# handset_adapter.net
KiCad netlist of a schematic drawn in Altium Designer
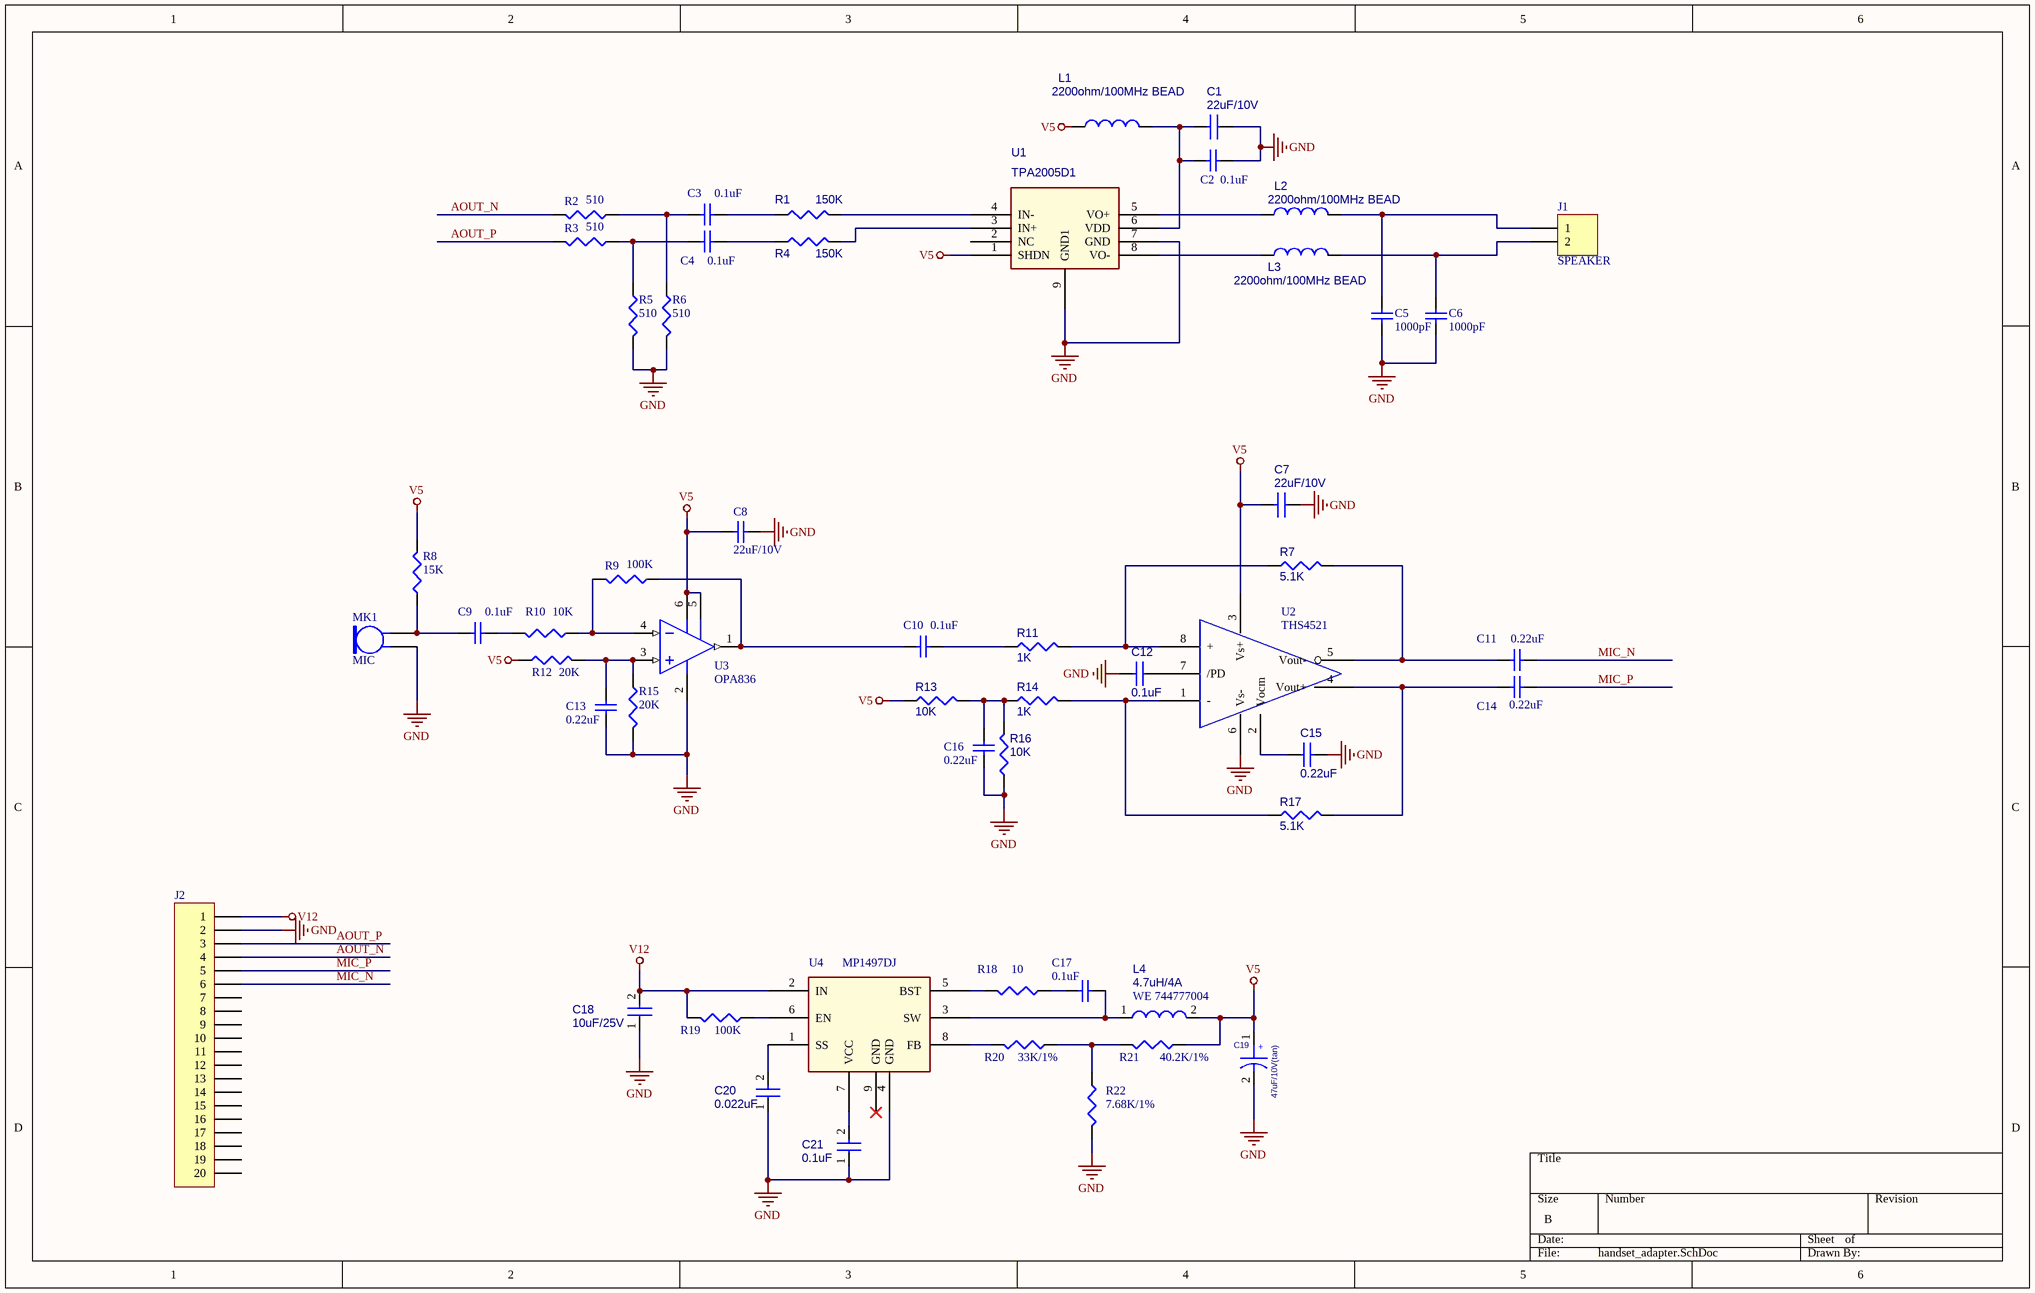
[diagram p0: handset_adapter.SchDoc]

(export (version "E")
  (design (tool "Eeschema 10.0.6"))
  (components
    (comp (ref "C1") (value "22uF/10V") (footprint "1210") (libsource (lib "*") (part "P_CAP NP")))
    (comp (ref "C2")
      (value "0.1uF")
      (footprint "0603")
      (description "Capacitor")
      (libsource (lib "Miscellaneous Devices") (part "Cap"))
    )
    (comp (ref "C3")
      (value "0.1uF")
      (footprint "0603")
      (description "Capacitor")
      (libsource (lib "Miscellaneous Devices") (part "Cap"))
    )
    (comp (ref "C4")
      (value "0.1uF")
      (footprint "0603")
      (description "Capacitor")
      (libsource (lib "Miscellaneous Devices") (part "Cap"))
    )
    (comp (ref "C5")
      (value "1000pF")
      (footprint "0603")
      (description "Capacitor")
      (libsource (lib "Miscellaneous Devices") (part "Cap"))
    )
    (comp (ref "C6")
      (value "1000pF")
      (footprint "0603")
      (description "Capacitor")
      (libsource (lib "Miscellaneous Devices") (part "Cap"))
    )
    (comp (ref "C7") (value "22uF/10V") (footprint "1210") (libsource (lib "*") (part "P_CAP NP")))
    (comp (ref "C8")
      (value "22uF/10V")
      (footprint "1210")
      (description "Capacitor")
      (libsource (lib "Miscellaneous Devices") (part "Cap"))
    )
    (comp (ref "C9")
      (value "0.1uF")
      (footprint "0603")
      (description "Capacitor")
      (libsource (lib "Miscellaneous Devices") (part "Cap"))
    )
    (comp (ref "C10")
      (value "0.1uF")
      (footprint "0603")
      (description "Capacitor")
      (libsource (lib "Miscellaneous Devices") (part "Cap"))
    )
    (comp (ref "C11")
      (value "0.22uF")
      (footprint "0603")
      (description "Capacitor")
      (libsource (lib "Miscellaneous Devices") (part "Cap"))
    )
    (comp (ref "C12") (value "0.1uF") (footprint "0603") (libsource (lib "*") (part "P_CAP NP")))
    (comp (ref "C13")
      (value "0.22uF")
      (footprint "0603")
      (description "Capacitor")
      (libsource (lib "Miscellaneous Devices") (part "Cap"))
    )
    (comp (ref "C14")
      (value "0.22uF")
      (footprint "0603")
      (description "Capacitor")
      (libsource (lib "Miscellaneous Devices") (part "Cap"))
    )
    (comp (ref "C15") (value "0.22uF") (footprint "0603") (libsource (lib "*") (part "P_CAP NP")))
    (comp (ref "C16")
      (value "0.22uF")
      (footprint "0603")
      (description "Capacitor")
      (libsource (lib "Miscellaneous Devices") (part "Cap"))
    )
    (comp (ref "C17")
      (value "0.1uF")
      (footprint "0603")
      (description "Capacitor")
      (libsource (lib "Miscellaneous Devices") (part "Cap"))
    )
    (comp (ref "C18") (value "10uF/25V") (footprint "1812") (libsource (lib "*") (part "CAP NP_Dup2")))
    (comp (ref "C19") (value "47uF/10V(tan)") (footprint "3528") (libsource (lib "*") (part "CAP WP")))
    (comp (ref "C20") (value "0.022uF") (footprint "0603") (libsource (lib "*") (part "CAP NP_Dup2")))
    (comp (ref "C21") (value "0.1uF") (footprint "0603") (libsource (lib "*") (part "CAP NP_Dup2")))
    (comp (ref "J1")
      (value "SPEAKER")
      (footprint "HDR1X2")
      (description "Header, 2-Pin")
      (fields (field (name "PUBLISHER") "Altium Limited"))
      (libsource (lib "Miscellaneous Connectors") (part "Header 2"))
    )
    (comp (ref "J2")
      (value "Header 20")
      (footprint "COMM-3MM-2X10")
      (description "Header, 20-Pin")
      (fields (field (name "PUBLISHER") "Altium Limited"))
      (libsource (lib "Miscellaneous Connectors") (part "Header 20"))
    )
    (comp (ref "L1")
      (value "2200ohm/100MHz BEAD")
      (description "IND,FBEAD,SO 1206,30@100MHz,3 AMPS")
      (libsource (lib "*") (part "INDUCTOR_0"))
    )
    (comp (ref "L2")
      (value "2200ohm/100MHz BEAD")
      (description "IND,FBEAD,SO 1206,30@100MHz,3 AMPS")
      (libsource (lib "*") (part "INDUCTOR_0"))
    )
    (comp (ref "L3")
      (value "2200ohm/100MHz BEAD")
      (description "IND,FBEAD,SO 1206,30@100MHz,3 AMPS")
      (libsource (lib "*") (part "INDUCTOR_0"))
    )
    (comp (ref "L4")
      (value "4.7uH/4A")
      (footprint "IND-4.7UH-4A")
      (fields (field (name "CODE") "WE 744777004"))
      (libsource (lib "*") (part "4.7UH_CDH2D09BNP-4R7MC_0.7A_20%"))
    )
    (comp (ref "MK1")
      (value "MIC")
      (footprint "HDR1X2")
      (description "Microphone")
      (libsource (lib "Miscellaneous Devices") (part "Mic2"))
    )
    (comp (ref "R1") (value "150K") (footprint "0603") (libsource (lib "*") (part "P_R")))
    (comp (ref "R2")
      (value "510")
      (footprint "0603")
      (description "Resistor")
      (libsource (lib "Miscellaneous Devices") (part "Res3"))
    )
    (comp (ref "R3")
      (value "510")
      (footprint "0603")
      (description "Resistor")
      (libsource (lib "Miscellaneous Devices") (part "Res3"))
    )
    (comp (ref "R4") (value "150K") (footprint "0603") (libsource (lib "*") (part "P_R")))
    (comp (ref "R5")
      (value "510")
      (footprint "0603")
      (description "Resistor")
      (libsource (lib "Miscellaneous Devices") (part "Res3"))
    )
    (comp (ref "R6")
      (value "510")
      (footprint "0603")
      (description "Resistor")
      (libsource (lib "Miscellaneous Devices") (part "Res3"))
    )
    (comp (ref "R7") (value "5.1K") (footprint "0603") (libsource (lib "*") (part "P_R")))
    (comp (ref "R8")
      (value "15K")
      (footprint "0603")
      (description "Resistor")
      (libsource (lib "Miscellaneous Devices") (part "Res3"))
    )
    (comp (ref "R9")
      (value "100K")
      (footprint "0603")
      (description "Resistor")
      (libsource (lib "Miscellaneous Devices") (part "Res3"))
    )
    (comp (ref "R10")
      (value "10K")
      (footprint "0603")
      (description "Resistor")
      (libsource (lib "Miscellaneous Devices") (part "Res3"))
    )
    (comp (ref "R11") (value "1K") (footprint "0603") (libsource (lib "*") (part "P_R")))
    (comp (ref "R12")
      (value "20K")
      (footprint "0603")
      (description "Resistor")
      (libsource (lib "Miscellaneous Devices") (part "Res3"))
    )
    (comp (ref "R13") (value "10K") (footprint "0603") (libsource (lib "*") (part "P_R")))
    (comp (ref "R14") (value "1K") (footprint "0603") (libsource (lib "*") (part "P_R")))
    (comp (ref "R15")
      (value "20K")
      (footprint "0603")
      (description "Resistor")
      (libsource (lib "Miscellaneous Devices") (part "Res3"))
    )
    (comp (ref "R16") (value "10K") (footprint "0603") (libsource (lib "*") (part "P_R")))
    (comp (ref "R17") (value "5.1K") (footprint "0603") (libsource (lib "*") (part "P_R")))
    (comp (ref "R18") (value "10") (footprint "0603") (libsource (lib "*") (part "CR16-1003FM")))
    (comp (ref "R19") (value "100K") (footprint "0603") (libsource (lib "*") (part "CR16-1003FM")))
    (comp (ref "R20") (value "33K/1%") (footprint "0603") (libsource (lib "*") (part "CR16-1003FM")))
    (comp (ref "R21") (value "40.2K/1%") (footprint "0603") (libsource (lib "*") (part "CR16-1003FM")))
    (comp (ref "R22") (value "7.68K/1%") (footprint "0603") (libsource (lib "*") (part "CR16-1003FM")))
    (comp (ref "U1") (value "TPA2005D1") (footprint "QFN-8") (libsource (lib "*") (part "TPA2005D1_3")))
    (comp (ref "U2") (value "THS4521") (footprint "SO8") (libsource (lib "Schlib") (part "THS4521")))
    (comp (ref "U3") (value "OPA836") (footprint "SOT23-6") (libsource (lib "Schlib") (part "OPA836")))
    (comp (ref "U4") (value "MP1497DJ") (footprint "TSOT23-8") (libsource (lib "*") (part "MP1482_5")))
  )
  (nets
    (net (code "1") (name "/AOUT_N") (class "Default")
      (node (ref "J2") (pin "4") (pinfunction "4_4") (pintype "passive"))
      (node (ref "R2") (pin "2") (pinfunction "2_2") (pintype "passive"))
    )
    (net (code "2") (name "/AOUT_P") (class "Default")
      (node (ref "J2") (pin "3") (pinfunction "3_3") (pintype "passive"))
      (node (ref "R3") (pin "2") (pinfunction "2_2") (pintype "passive"))
    )
    (net (code "3") (name "/MIC_N") (class "Default")
      (node (ref "C11") (pin "1") (pinfunction "1_1") (pintype "passive"))
      (node (ref "J2") (pin "6") (pinfunction "6_6") (pintype "passive"))
    )
    (net (code "4") (name "/MIC_P") (class "Default")
      (node (ref "C14") (pin "1") (pinfunction "1_1") (pintype "passive"))
      (node (ref "J2") (pin "5") (pinfunction "5_5") (pintype "passive"))
    )
    (net (code "5") (name "GND") (class "Default")
      (node (ref "C1") (pin "1") (pinfunction "1_1") (pintype "passive"))
      (node (ref "C12") (pin "2") (pinfunction "2_2") (pintype "passive"))
      (node (ref "C13") (pin "1") (pinfunction "1_1") (pintype "passive"))
      (node (ref "C15") (pin "2") (pinfunction "2_2") (pintype "passive"))
      (node (ref "C16") (pin "1") (pinfunction "1_1") (pintype "passive"))
      (node (ref "C18") (pin "1") (pinfunction "1_1") (pintype "passive"))
      (node (ref "C19") (pin "2") (pinfunction "2_2") (pintype "passive"))
      (node (ref "C2") (pin "2") (pinfunction "2_2") (pintype "passive"))
      (node (ref "C20") (pin "1") (pinfunction "1_1") (pintype "passive"))
      (node (ref "C21") (pin "1") (pinfunction "1_1") (pintype "passive"))
      (node (ref "C5") (pin "1") (pinfunction "1_1") (pintype "passive"))
      (node (ref "C6") (pin "1") (pinfunction "1_1") (pintype "passive"))
      (node (ref "C7") (pin "1") (pinfunction "1_1") (pintype "passive"))
      (node (ref "C8") (pin "1") (pinfunction "1_1") (pintype "passive"))
      (node (ref "J2") (pin "2") (pinfunction "2_2") (pintype "passive"))
      (node (ref "MK1") (pin "2") (pinfunction "2_2") (pintype "passive"))
      (node (ref "R15") (pin "2") (pinfunction "2_2") (pintype "passive"))
      (node (ref "R16") (pin "1") (pinfunction "1_1") (pintype "passive"))
      (node (ref "R22") (pin "2") (pinfunction "2_2") (pintype "passive"))
      (node (ref "R5") (pin "2") (pinfunction "2_2") (pintype "passive"))
      (node (ref "R6") (pin "2") (pinfunction "2_2") (pintype "passive"))
      (node (ref "U1") (pin "7") (pinfunction "GND_7") (pintype "passive"))
      (node (ref "U1") (pin "9") (pinfunction "GND1_9") (pintype "passive"))
      (node (ref "U2") (pin "6") (pinfunction "Vs-_6") (pintype "passive"))
      (node (ref "U3") (pin "2") (pinfunction "V-_2") (pintype "power_in"))
      (node (ref "U4") (pin "4") (pinfunction "GND_4") (pintype "power_in"))
    )
    (net (code "6") (name "Net-(C3-Pad1)") (class "Default")
      (node (ref "C3") (pin "1") (pinfunction "1_1") (pintype "passive"))
      (node (ref "R2") (pin "1") (pinfunction "1_1") (pintype "passive"))
      (node (ref "R6") (pin "1") (pinfunction "1_1") (pintype "passive"))
    )
    (net (code "7") (name "Net-(C3-Pad2)") (class "Default")
      (node (ref "C3") (pin "2") (pinfunction "2_2") (pintype "passive"))
      (node (ref "R1") (pin "1") (pinfunction "1_1") (pintype "passive"))
    )
    (net (code "8") (name "Net-(C4-Pad1)") (class "Default")
      (node (ref "C4") (pin "1") (pinfunction "1_1") (pintype "passive"))
      (node (ref "R3") (pin "1") (pinfunction "1_1") (pintype "passive"))
      (node (ref "R5") (pin "1") (pinfunction "1_1") (pintype "passive"))
    )
    (net (code "9") (name "Net-(C4-Pad2)") (class "Default")
      (node (ref "C4") (pin "2") (pinfunction "2_2") (pintype "passive"))
      (node (ref "R4") (pin "1") (pinfunction "1_1") (pintype "passive"))
    )
    (net (code "10") (name "Net-(C5-Pad2)") (class "Default")
      (node (ref "C5") (pin "2") (pinfunction "2_2") (pintype "passive"))
      (node (ref "J1") (pin "1") (pinfunction "1_1") (pintype "passive"))
      (node (ref "L2") (pin "2") (pinfunction "2_2") (pintype "passive"))
    )
    (net (code "11") (name "Net-(C6-Pad2)") (class "Default")
      (node (ref "C6") (pin "2") (pinfunction "2_2") (pintype "passive"))
      (node (ref "J1") (pin "2") (pinfunction "2_2") (pintype "passive"))
      (node (ref "L3") (pin "2") (pinfunction "2_2") (pintype "passive"))
    )
    (net (code "12") (name "Net-(C9-Pad1)") (class "Default")
      (node (ref "C9") (pin "1") (pinfunction "1_1") (pintype "passive"))
      (node (ref "MK1") (pin "1") (pinfunction "1_1") (pintype "passive"))
      (node (ref "R8") (pin "1") (pinfunction "1_1") (pintype "passive"))
    )
    (net (code "13") (name "Net-(C9-Pad2)") (class "Default")
      (node (ref "C9") (pin "2") (pinfunction "2_2") (pintype "passive"))
      (node (ref "R10") (pin "2") (pinfunction "2_2") (pintype "passive"))
    )
    (net (code "14") (name "Net-(C10-Pad2)") (class "Default")
      (node (ref "C10") (pin "2") (pinfunction "2_2") (pintype "passive"))
      (node (ref "R11") (pin "1") (pinfunction "1_1") (pintype "passive"))
    )
    (net (code "15") (name "Net-(C16-Pad2)") (class "Default")
      (node (ref "C16") (pin "2") (pinfunction "2_2") (pintype "passive"))
      (node (ref "R13") (pin "2") (pinfunction "2_2") (pintype "passive"))
      (node (ref "R14") (pin "1") (pinfunction "1_1") (pintype "passive"))
      (node (ref "R16") (pin "2") (pinfunction "2_2") (pintype "passive"))
    )
    (net (code "16") (name "Net-(C17-Pad2)") (class "Default")
      (node (ref "C17") (pin "2") (pinfunction "2_2") (pintype "passive"))
      (node (ref "R18") (pin "1") (pinfunction "1_1") (pintype "passive"))
    )
    (net (code "17") (name "Net-(R20-Pad1)") (class "Default")
      (node (ref "R20") (pin "1") (pinfunction "1_1") (pintype "passive"))
      (node (ref "R21") (pin "2") (pinfunction "2_2") (pintype "passive"))
      (node (ref "R22") (pin "1") (pinfunction "1_1") (pintype "passive"))
    )
    (net (code "18") (name "Net-(U1-IN+)") (class "Default")
      (node (ref "R4") (pin "2") (pinfunction "2_2") (pintype "passive"))
      (node (ref "U1") (pin "3") (pinfunction "IN+_3") (pintype "passive"))
    )
    (net (code "19") (name "Net-(U1-IN-)") (class "Default")
      (node (ref "R1") (pin "2") (pinfunction "2_2") (pintype "passive"))
      (node (ref "U1") (pin "4") (pinfunction "IN-_4") (pintype "passive"))
    )
    (net (code "20") (name "Net-(U1-VDD)") (class "Default")
      (node (ref "C1") (pin "2") (pinfunction "2_2") (pintype "passive"))
      (node (ref "C2") (pin "1") (pinfunction "1_1") (pintype "passive"))
      (node (ref "L1") (pin "2") (pinfunction "2_2") (pintype "passive"))
      (node (ref "U1") (pin "6") (pinfunction "VDD_6") (pintype "passive"))
    )
    (net (code "21") (name "Net-(U1-VO+)") (class "Default")
      (node (ref "L2") (pin "1") (pinfunction "1_1") (pintype "passive"))
      (node (ref "U1") (pin "5") (pinfunction "VO+_5") (pintype "passive"))
    )
    (net (code "22") (name "Net-(U1-VO-)") (class "Default")
      (node (ref "L3") (pin "1") (pinfunction "1_1") (pintype "passive"))
      (node (ref "U1") (pin "8") (pinfunction "VO-_8") (pintype "passive"))
    )
    (net (code "23") (name "Net-(U2-+)") (class "Default")
      (node (ref "R11") (pin "2") (pinfunction "2_2") (pintype "passive"))
      (node (ref "R7") (pin "1") (pinfunction "1_1") (pintype "passive"))
      (node (ref "U2") (pin "8") (pinfunction "+_8") (pintype "passive"))
    )
    (net (code "24") (name "Net-(U2--)") (class "Default")
      (node (ref "R14") (pin "2") (pinfunction "2_2") (pintype "passive"))
      (node (ref "R17") (pin "1") (pinfunction "1_1") (pintype "passive"))
      (node (ref "U2") (pin "1") (pinfunction "-_1") (pintype "passive"))
    )
    (net (code "25") (name "Net-(U2-Vocm)") (class "Default")
      (node (ref "C15") (pin "1") (pinfunction "1_1") (pintype "passive"))
      (node (ref "U2") (pin "2") (pinfunction "Vocm_2") (pintype "passive"))
    )
    (net (code "26") (name "Net-(U2-Vout+)") (class "Default")
      (node (ref "C14") (pin "2") (pinfunction "2_2") (pintype "passive"))
      (node (ref "R17") (pin "2") (pinfunction "2_2") (pintype "passive"))
      (node (ref "U2") (pin "4") (pinfunction "Vout+_4") (pintype "passive"))
    )
    (net (code "27") (name "Net-(U2-Vout-)") (class "Default")
      (node (ref "C11") (pin "2") (pinfunction "2_2") (pintype "passive"))
      (node (ref "R7") (pin "2") (pinfunction "2_2") (pintype "passive"))
      (node (ref "U2") (pin "5") (pinfunction "Vout-_5") (pintype "passive"))
    )
    (net (code "28") (name "Net-(U2-{slash}PD)") (class "Default")
      (node (ref "C12") (pin "1") (pinfunction "1_1") (pintype "passive"))
      (node (ref "U2") (pin "7") (pinfunction "/PD_7") (pintype "passive"))
    )
    (net (code "29") (name "Net-(U3-IN+)") (class "Default")
      (node (ref "C13") (pin "2") (pinfunction "2_2") (pintype "passive"))
      (node (ref "R12") (pin "2") (pinfunction "2_2") (pintype "passive"))
      (node (ref "R15") (pin "1") (pinfunction "1_1") (pintype "passive"))
      (node (ref "U3") (pin "3") (pinfunction "IN+_3") (pintype "input"))
    )
    (net (code "30") (name "Net-(U3-IN-)") (class "Default")
      (node (ref "R10") (pin "1") (pinfunction "1_1") (pintype "passive"))
      (node (ref "R9") (pin "2") (pinfunction "2_2") (pintype "passive"))
      (node (ref "U3") (pin "4") (pinfunction "IN-_4") (pintype "input"))
    )
    (net (code "31") (name "Net-(U3-OUT)") (class "Default")
      (node (ref "C10") (pin "1") (pinfunction "1_1") (pintype "passive"))
      (node (ref "R9") (pin "1") (pinfunction "1_1") (pintype "passive"))
      (node (ref "U3") (pin "1") (pinfunction "OUT_1") (pintype "output"))
    )
    (net (code "32") (name "Net-(U4-BST)") (class "Default")
      (node (ref "R18") (pin "2") (pinfunction "2_2") (pintype "passive"))
      (node (ref "U4") (pin "5") (pinfunction "BST_5") (pintype "passive"))
    )
    (net (code "33") (name "Net-(U4-EN)") (class "Default")
      (node (ref "R19") (pin "1") (pinfunction "1_1") (pintype "passive"))
      (node (ref "U4") (pin "6") (pinfunction "EN_6") (pintype "passive"))
    )
    (net (code "34") (name "Net-(U4-FB)") (class "Default")
      (node (ref "R20") (pin "2") (pinfunction "2_2") (pintype "passive"))
      (node (ref "U4") (pin "8") (pinfunction "FB_8") (pintype "passive"))
    )
    (net (code "35") (name "Net-(U4-SS)") (class "Default")
      (node (ref "C20") (pin "2") (pinfunction "2_2") (pintype "passive"))
      (node (ref "U4") (pin "1") (pinfunction "SS_1") (pintype "passive"))
    )
    (net (code "36") (name "Net-(U4-SW)") (class "Default")
      (node (ref "C17") (pin "1") (pinfunction "1_1") (pintype "passive"))
      (node (ref "L4") (pin "1") (pinfunction "1_1") (pintype "passive"))
      (node (ref "U4") (pin "3") (pinfunction "SW_3") (pintype "passive"))
    )
    (net (code "37") (name "Net-(U4-VCC)") (class "Default")
      (node (ref "C21") (pin "2") (pinfunction "2_2") (pintype "passive"))
      (node (ref "U4") (pin "7") (pinfunction "VCC_7") (pintype "passive"))
    )
    (net (code "38") (name "V5") (class "Default")
      (node (ref "C19") (pin "1") (pinfunction "1_1") (pintype "passive"))
      (node (ref "C7") (pin "2") (pinfunction "2_2") (pintype "passive"))
      (node (ref "C8") (pin "2") (pinfunction "2_2") (pintype "passive"))
      (node (ref "L1") (pin "1") (pinfunction "1_1") (pintype "passive"))
      (node (ref "L4") (pin "2") (pinfunction "2_2") (pintype "passive"))
      (node (ref "R12") (pin "1") (pinfunction "1_1") (pintype "passive"))
      (node (ref "R13") (pin "1") (pinfunction "1_1") (pintype "passive"))
      (node (ref "R21") (pin "1") (pinfunction "1_1") (pintype "passive"))
      (node (ref "R8") (pin "2") (pinfunction "2_2") (pintype "passive"))
      (node (ref "U1") (pin "1") (pinfunction "SHDN_1") (pintype "passive"))
      (node (ref "U2") (pin "3") (pinfunction "Vs+_3") (pintype "passive"))
      (node (ref "U3") (pin "5") (pinfunction "~{P}D_5") (pintype "passive"))
      (node (ref "U3") (pin "6") (pinfunction "V+_6") (pintype "power_in"))
    )
    (net (code "39") (name "V12") (class "Default")
      (node (ref "C18") (pin "2") (pinfunction "2_2") (pintype "passive"))
      (node (ref "J2") (pin "1") (pinfunction "1_1") (pintype "passive"))
      (node (ref "R19") (pin "2") (pinfunction "2_2") (pintype "passive"))
      (node (ref "U4") (pin "2") (pinfunction "IN_2") (pintype "passive"))
    )
    (net (code "40") (name "unconnected-(J2-Pad7)") (class "Default")
      (node (ref "J2") (pin "7") (pinfunction "7_7") (pintype "passive"))
    )
    (net (code "41") (name "unconnected-(J2-Pad8)") (class "Default")
      (node (ref "J2") (pin "8") (pinfunction "8_8") (pintype "passive"))
    )
    (net (code "42") (name "unconnected-(J2-Pad9)") (class "Default")
      (node (ref "J2") (pin "9") (pinfunction "9_9") (pintype "passive"))
    )
    (net (code "43") (name "unconnected-(J2-Pad10)") (class "Default")
      (node (ref "J2") (pin "10") (pinfunction "10_10") (pintype "passive"))
    )
    (net (code "44") (name "unconnected-(J2-Pad11)") (class "Default")
      (node (ref "J2") (pin "11") (pinfunction "11_11") (pintype "passive"))
    )
    (net (code "45") (name "unconnected-(J2-Pad12)") (class "Default")
      (node (ref "J2") (pin "12") (pinfunction "12_12") (pintype "passive"))
    )
    (net (code "46") (name "unconnected-(J2-Pad13)") (class "Default")
      (node (ref "J2") (pin "13") (pinfunction "13_13") (pintype "passive"))
    )
    (net (code "47") (name "unconnected-(J2-Pad14)") (class "Default")
      (node (ref "J2") (pin "14") (pinfunction "14_14") (pintype "passive"))
    )
    (net (code "48") (name "unconnected-(J2-Pad15)") (class "Default")
      (node (ref "J2") (pin "15") (pinfunction "15_15") (pintype "passive"))
    )
    (net (code "49") (name "unconnected-(J2-Pad16)") (class "Default")
      (node (ref "J2") (pin "16") (pinfunction "16_16") (pintype "passive"))
    )
    (net (code "50") (name "unconnected-(J2-Pad17)") (class "Default")
      (node (ref "J2") (pin "17") (pinfunction "17_17") (pintype "passive"))
    )
    (net (code "51") (name "unconnected-(J2-Pad18)") (class "Default")
      (node (ref "J2") (pin "18") (pinfunction "18_18") (pintype "passive"))
    )
    (net (code "52") (name "unconnected-(J2-Pad19)") (class "Default")
      (node (ref "J2") (pin "19") (pinfunction "19_19") (pintype "passive"))
    )
    (net (code "53") (name "unconnected-(J2-Pad20)") (class "Default")
      (node (ref "J2") (pin "20") (pinfunction "20_20") (pintype "passive"))
    )
    (net (code "54") (name "unconnected-(U1-NC-Pad2)") (class "Default")
      (node (ref "U1") (pin "2") (pinfunction "NC_2") (pintype "passive"))
    )
    (net (code "55") (name "unconnected-(U4-GND-Pad9)") (class "Default")
      (node (ref "U4") (pin "9") (pinfunction "GND_9") (pintype "power_in+no_connect"))
    )
  )
)
